# Bottom_board.net
KiCad netlist of a schematic drawn in Altium Designer
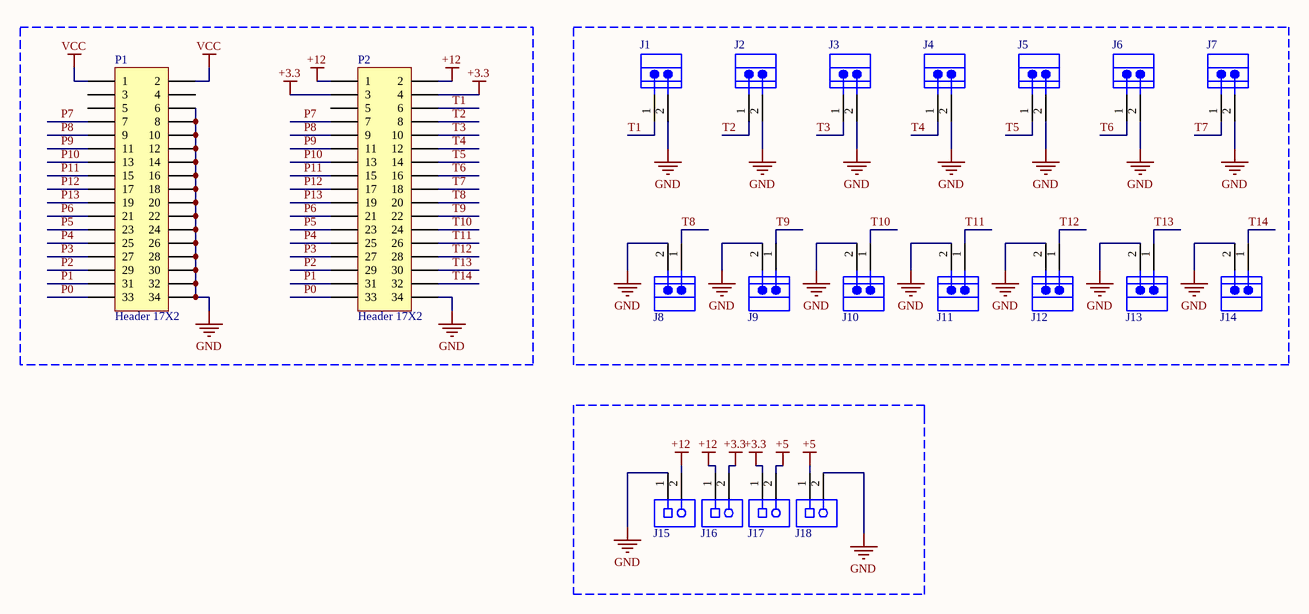
[diagram p0: Bottom_board.SchDoc]

(export (version "E")
  (design (tool "Eeschema 10.0.6"))
  (components
    (comp (ref "J1")
      (value "~")
      (footprint "KF350-3.5-02P")
      (fields
        (field (name "MANUFACTURER") "Cixi KaiFeng")
        (field (name "PARTNUMBER") "KF120-02P-14")
        (field (name "CONTACT") "Brass")
      )
      (libsource (lib "altium-import") (part "root_0_Terminal_2_"))
    )
    (comp (ref "J2")
      (value "~")
      (footprint "KF350-3.5-02P")
      (fields
        (field (name "MANUFACTURER") "Cixi KaiFeng")
        (field (name "PARTNUMBER") "KF120-02P-14")
        (field (name "CONTACT") "Brass")
      )
      (libsource (lib "altium-import") (part "root_0_Terminal_2_"))
    )
    (comp (ref "J3")
      (value "~")
      (footprint "KF350-3.5-02P")
      (fields
        (field (name "MANUFACTURER") "Cixi KaiFeng")
        (field (name "PARTNUMBER") "KF120-02P-14")
        (field (name "CONTACT") "Brass")
      )
      (libsource (lib "altium-import") (part "root_0_Terminal_2_"))
    )
    (comp (ref "J4")
      (value "~")
      (footprint "KF350-3.5-02P")
      (fields
        (field (name "MANUFACTURER") "Cixi KaiFeng")
        (field (name "PARTNUMBER") "KF120-02P-14")
        (field (name "CONTACT") "Brass")
      )
      (libsource (lib "altium-import") (part "root_0_Terminal_2_"))
    )
    (comp (ref "J5")
      (value "~")
      (footprint "KF350-3.5-02P")
      (fields
        (field (name "MANUFACTURER") "Cixi KaiFeng")
        (field (name "PARTNUMBER") "KF120-02P-14")
        (field (name "CONTACT") "Brass")
      )
      (libsource (lib "altium-import") (part "root_0_Terminal_2_"))
    )
    (comp (ref "J6")
      (value "~")
      (footprint "KF350-3.5-02P")
      (fields
        (field (name "MANUFACTURER") "Cixi KaiFeng")
        (field (name "PARTNUMBER") "KF120-02P-14")
        (field (name "CONTACT") "Brass")
      )
      (libsource (lib "altium-import") (part "root_0_Terminal_2_"))
    )
    (comp (ref "J7")
      (value "~")
      (footprint "KF350-3.5-02P")
      (fields
        (field (name "MANUFACTURER") "Cixi KaiFeng")
        (field (name "PARTNUMBER") "KF120-02P-14")
        (field (name "CONTACT") "Brass")
      )
      (libsource (lib "altium-import") (part "root_0_Terminal_2_"))
    )
    (comp (ref "J8")
      (value "~")
      (footprint "KF350-3.5-02P")
      (fields
        (field (name "MANUFACTURER") "Cixi KaiFeng")
        (field (name "PARTNUMBER") "KF120-02P-14")
        (field (name "CONTACT") "Brass")
      )
      (libsource (lib "altium-import") (part "root_2_Terminal_2_"))
    )
    (comp (ref "J9")
      (value "~")
      (footprint "KF350-3.5-02P")
      (fields
        (field (name "MANUFACTURER") "Cixi KaiFeng")
        (field (name "PARTNUMBER") "KF120-02P-14")
        (field (name "CONTACT") "Brass")
      )
      (libsource (lib "altium-import") (part "root_2_Terminal_2_"))
    )
    (comp (ref "J10")
      (value "~")
      (footprint "KF350-3.5-02P")
      (fields
        (field (name "MANUFACTURER") "Cixi KaiFeng")
        (field (name "PARTNUMBER") "KF120-02P-14")
        (field (name "CONTACT") "Brass")
      )
      (libsource (lib "altium-import") (part "root_2_Terminal_2_"))
    )
    (comp (ref "J11")
      (value "~")
      (footprint "KF350-3.5-02P")
      (fields
        (field (name "MANUFACTURER") "Cixi KaiFeng")
        (field (name "PARTNUMBER") "KF120-02P-14")
        (field (name "CONTACT") "Brass")
      )
      (libsource (lib "altium-import") (part "root_2_Terminal_2_"))
    )
    (comp (ref "J12")
      (value "~")
      (footprint "KF350-3.5-02P")
      (fields
        (field (name "MANUFACTURER") "Cixi KaiFeng")
        (field (name "PARTNUMBER") "KF120-02P-14")
        (field (name "CONTACT") "Brass")
      )
      (libsource (lib "altium-import") (part "root_2_Terminal_2_"))
    )
    (comp (ref "J13")
      (value "~")
      (footprint "KF350-3.5-02P")
      (fields
        (field (name "MANUFACTURER") "Cixi KaiFeng")
        (field (name "PARTNUMBER") "KF120-02P-14")
        (field (name "CONTACT") "Brass")
      )
      (libsource (lib "altium-import") (part "root_2_Terminal_2_"))
    )
    (comp (ref "J14")
      (value "~")
      (footprint "KF350-3.5-02P")
      (fields
        (field (name "MANUFACTURER") "Cixi KaiFeng")
        (field (name "PARTNUMBER") "KF120-02P-14")
        (field (name "CONTACT") "Brass")
      )
      (libsource (lib "altium-import") (part "root_2_Terminal_2_"))
    )
    (comp (ref "J15")
      (value "~")
      (footprint "PHOE-1729128-2_V")
      (description "PCB Terminal Block, 13.5 A, 400 V, 2-Pin THD, RoHS, Bulk")
      (fields (field (name "PARTNUMBER") "1729128") (field (name "MANUFACTURER") "Phoenix Contact"))
      (libsource (lib "altium-import") (part "root_3_mirrored_Terminal_2_Green_"))
    )
    (comp (ref "J16")
      (value "~")
      (footprint "PHOE-1729128-2_V")
      (description "PCB Terminal Block, 13.5 A, 400 V, 2-Pin THD, RoHS, Bulk")
      (fields (field (name "PARTNUMBER") "1729128") (field (name "MANUFACTURER") "Phoenix Contact"))
      (libsource (lib "altium-import") (part "root_3_mirrored_Terminal_2_Green_"))
    )
    (comp (ref "J17")
      (value "~")
      (footprint "PHOE-1729128-2_V")
      (description "PCB Terminal Block, 13.5 A, 400 V, 2-Pin THD, RoHS, Bulk")
      (fields (field (name "PARTNUMBER") "1729128") (field (name "MANUFACTURER") "Phoenix Contact"))
      (libsource (lib "altium-import") (part "root_3_mirrored_Terminal_2_Green_"))
    )
    (comp (ref "J18")
      (value "~")
      (footprint "PHOE-1729128-2_V")
      (description "PCB Terminal Block, 13.5 A, 400 V, 2-Pin THD, RoHS, Bulk")
      (fields (field (name "PARTNUMBER") "1729128") (field (name "MANUFACTURER") "Phoenix Contact"))
      (libsource (lib "altium-import") (part "root_3_mirrored_Terminal_2_Green_"))
    )
    (comp (ref "P1")
      (value "Header 17X2")
      (footprint "HDR2X17")
      (description "Header, 17-Pin, Dual row")
      (fields (field (name "PUBLISHER") "Altium Limited"))
      (libsource (lib "altium-import") (part "root_0_Header 17X2_"))
    )
    (comp (ref "P2")
      (value "Header 17X2")
      (footprint "HDR2X17-PBD")
      (description "Header, 17-Pin, Dual row")
      (fields (field (name "PUBLISHER") "Altium Limited"))
      (libsource (lib "altium-import") (part "root_0_Header 17X2_"))
    )
  )
  (nets
    (net (code "1") (name "+3.3") (class "Default")
      (node (ref "J16") (pin "2") (pinfunction "2_2") (pintype "passive"))
      (node (ref "J17") (pin "1") (pinfunction "1_1") (pintype "passive"))
      (node (ref "P2") (pin "3") (pinfunction "3_3") (pintype "passive"))
      (node (ref "P2") (pin "4") (pinfunction "4_4") (pintype "passive"))
    )
    (net (code "2") (name "+5") (class "Default")
      (node (ref "J17") (pin "2") (pinfunction "2_2") (pintype "passive"))
      (node (ref "J18") (pin "1") (pinfunction "1_1") (pintype "passive"))
    )
    (net (code "3") (name "+12") (class "Default")
      (node (ref "J15") (pin "2") (pinfunction "2_2") (pintype "passive"))
      (node (ref "J16") (pin "1") (pinfunction "1_1") (pintype "passive"))
      (node (ref "P2") (pin "1") (pinfunction "1_1") (pintype "passive"))
      (node (ref "P2") (pin "2") (pinfunction "2_2") (pintype "passive"))
    )
    (net (code "4") (name "/P0") (class "Default")
      (node (ref "P1") (pin "33") (pinfunction "33_33") (pintype "passive"))
      (node (ref "P2") (pin "33") (pinfunction "33_33") (pintype "passive"))
    )
    (net (code "5") (name "/P1") (class "Default")
      (node (ref "P1") (pin "31") (pinfunction "31_31") (pintype "passive"))
      (node (ref "P2") (pin "31") (pinfunction "31_31") (pintype "passive"))
    )
    (net (code "6") (name "/P2") (class "Default")
      (node (ref "P1") (pin "29") (pinfunction "29_29") (pintype "passive"))
      (node (ref "P2") (pin "29") (pinfunction "29_29") (pintype "passive"))
    )
    (net (code "7") (name "/P3") (class "Default")
      (node (ref "P1") (pin "27") (pinfunction "27_27") (pintype "passive"))
      (node (ref "P2") (pin "27") (pinfunction "27_27") (pintype "passive"))
    )
    (net (code "8") (name "/P4") (class "Default")
      (node (ref "P1") (pin "25") (pinfunction "25_25") (pintype "passive"))
      (node (ref "P2") (pin "25") (pinfunction "25_25") (pintype "passive"))
    )
    (net (code "9") (name "/P5") (class "Default")
      (node (ref "P1") (pin "23") (pinfunction "23_23") (pintype "passive"))
      (node (ref "P2") (pin "23") (pinfunction "23_23") (pintype "passive"))
    )
    (net (code "10") (name "/P6") (class "Default")
      (node (ref "P1") (pin "21") (pinfunction "21_21") (pintype "passive"))
      (node (ref "P2") (pin "21") (pinfunction "21_21") (pintype "passive"))
    )
    (net (code "11") (name "/P7") (class "Default")
      (node (ref "P1") (pin "7") (pinfunction "7_7") (pintype "passive"))
      (node (ref "P2") (pin "7") (pinfunction "7_7") (pintype "passive"))
    )
    (net (code "12") (name "/P8") (class "Default")
      (node (ref "P1") (pin "9") (pinfunction "9_9") (pintype "passive"))
      (node (ref "P2") (pin "9") (pinfunction "9_9") (pintype "passive"))
    )
    (net (code "13") (name "/P9") (class "Default")
      (node (ref "P1") (pin "11") (pinfunction "11_11") (pintype "passive"))
      (node (ref "P2") (pin "11") (pinfunction "11_11") (pintype "passive"))
    )
    (net (code "14") (name "/P10") (class "Default")
      (node (ref "P1") (pin "13") (pinfunction "13_13") (pintype "passive"))
      (node (ref "P2") (pin "13") (pinfunction "13_13") (pintype "passive"))
    )
    (net (code "15") (name "/P11") (class "Default")
      (node (ref "P1") (pin "15") (pinfunction "15_15") (pintype "passive"))
      (node (ref "P2") (pin "15") (pinfunction "15_15") (pintype "passive"))
    )
    (net (code "16") (name "/P12") (class "Default")
      (node (ref "P1") (pin "17") (pinfunction "17_17") (pintype "passive"))
      (node (ref "P2") (pin "17") (pinfunction "17_17") (pintype "passive"))
    )
    (net (code "17") (name "/P13") (class "Default")
      (node (ref "P1") (pin "19") (pinfunction "19_19") (pintype "passive"))
      (node (ref "P2") (pin "19") (pinfunction "19_19") (pintype "passive"))
    )
    (net (code "18") (name "/T1") (class "Default")
      (node (ref "J1") (pin "1") (pinfunction "1_1") (pintype "passive"))
      (node (ref "P2") (pin "6") (pinfunction "6_6") (pintype "passive"))
    )
    (net (code "19") (name "/T2") (class "Default")
      (node (ref "J2") (pin "1") (pinfunction "1_1") (pintype "passive"))
      (node (ref "P2") (pin "8") (pinfunction "8_8") (pintype "passive"))
    )
    (net (code "20") (name "/T3") (class "Default")
      (node (ref "J3") (pin "1") (pinfunction "1_1") (pintype "passive"))
      (node (ref "P2") (pin "10") (pinfunction "10_10") (pintype "passive"))
    )
    (net (code "21") (name "/T4") (class "Default")
      (node (ref "J4") (pin "1") (pinfunction "1_1") (pintype "passive"))
      (node (ref "P2") (pin "12") (pinfunction "12_12") (pintype "passive"))
    )
    (net (code "22") (name "/T5") (class "Default")
      (node (ref "J5") (pin "1") (pinfunction "1_1") (pintype "passive"))
      (node (ref "P2") (pin "14") (pinfunction "14_14") (pintype "passive"))
    )
    (net (code "23") (name "/T6") (class "Default")
      (node (ref "J6") (pin "1") (pinfunction "1_1") (pintype "passive"))
      (node (ref "P2") (pin "16") (pinfunction "16_16") (pintype "passive"))
    )
    (net (code "24") (name "/T7") (class "Default")
      (node (ref "J7") (pin "1") (pinfunction "1_1") (pintype "passive"))
      (node (ref "P2") (pin "18") (pinfunction "18_18") (pintype "passive"))
    )
    (net (code "25") (name "/T8") (class "Default")
      (node (ref "J8") (pin "1") (pinfunction "1_1") (pintype "passive"))
      (node (ref "P2") (pin "20") (pinfunction "20_20") (pintype "passive"))
    )
    (net (code "26") (name "/T9") (class "Default")
      (node (ref "J9") (pin "1") (pinfunction "1_1") (pintype "passive"))
      (node (ref "P2") (pin "22") (pinfunction "22_22") (pintype "passive"))
    )
    (net (code "27") (name "/T10") (class "Default")
      (node (ref "J10") (pin "1") (pinfunction "1_1") (pintype "passive"))
      (node (ref "P2") (pin "24") (pinfunction "24_24") (pintype "passive"))
    )
    (net (code "28") (name "/T11") (class "Default")
      (node (ref "J11") (pin "1") (pinfunction "1_1") (pintype "passive"))
      (node (ref "P2") (pin "26") (pinfunction "26_26") (pintype "passive"))
    )
    (net (code "29") (name "/T12") (class "Default")
      (node (ref "J12") (pin "1") (pinfunction "1_1") (pintype "passive"))
      (node (ref "P2") (pin "28") (pinfunction "28_28") (pintype "passive"))
    )
    (net (code "30") (name "/T13") (class "Default")
      (node (ref "J13") (pin "1") (pinfunction "1_1") (pintype "passive"))
      (node (ref "P2") (pin "30") (pinfunction "30_30") (pintype "passive"))
    )
    (net (code "31") (name "/T14") (class "Default")
      (node (ref "J14") (pin "1") (pinfunction "1_1") (pintype "passive"))
      (node (ref "P2") (pin "32") (pinfunction "32_32") (pintype "passive"))
    )
    (net (code "32") (name "GND") (class "Default")
      (node (ref "J1") (pin "2") (pinfunction "2_2") (pintype "passive"))
      (node (ref "J10") (pin "2") (pinfunction "2_2") (pintype "passive"))
      (node (ref "J11") (pin "2") (pinfunction "2_2") (pintype "passive"))
      (node (ref "J12") (pin "2") (pinfunction "2_2") (pintype "passive"))
      (node (ref "J13") (pin "2") (pinfunction "2_2") (pintype "passive"))
      (node (ref "J14") (pin "2") (pinfunction "2_2") (pintype "passive"))
      (node (ref "J15") (pin "1") (pinfunction "1_1") (pintype "passive"))
      (node (ref "J18") (pin "2") (pinfunction "2_2") (pintype "passive"))
      (node (ref "J2") (pin "2") (pinfunction "2_2") (pintype "passive"))
      (node (ref "J3") (pin "2") (pinfunction "2_2") (pintype "passive"))
      (node (ref "J4") (pin "2") (pinfunction "2_2") (pintype "passive"))
      (node (ref "J5") (pin "2") (pinfunction "2_2") (pintype "passive"))
      (node (ref "J6") (pin "2") (pinfunction "2_2") (pintype "passive"))
      (node (ref "J7") (pin "2") (pinfunction "2_2") (pintype "passive"))
      (node (ref "J8") (pin "2") (pinfunction "2_2") (pintype "passive"))
      (node (ref "J9") (pin "2") (pinfunction "2_2") (pintype "passive"))
      (node (ref "P1") (pin "10") (pinfunction "10_10") (pintype "passive"))
      (node (ref "P1") (pin "12") (pinfunction "12_12") (pintype "passive"))
      (node (ref "P1") (pin "14") (pinfunction "14_14") (pintype "passive"))
      (node (ref "P1") (pin "16") (pinfunction "16_16") (pintype "passive"))
      (node (ref "P1") (pin "18") (pinfunction "18_18") (pintype "passive"))
      (node (ref "P1") (pin "20") (pinfunction "20_20") (pintype "passive"))
      (node (ref "P1") (pin "22") (pinfunction "22_22") (pintype "passive"))
      (node (ref "P1") (pin "24") (pinfunction "24_24") (pintype "passive"))
      (node (ref "P1") (pin "26") (pinfunction "26_26") (pintype "passive"))
      (node (ref "P1") (pin "28") (pinfunction "28_28") (pintype "passive"))
      (node (ref "P1") (pin "30") (pinfunction "30_30") (pintype "passive"))
      (node (ref "P1") (pin "32") (pinfunction "32_32") (pintype "passive"))
      (node (ref "P1") (pin "34") (pinfunction "34_34") (pintype "passive"))
      (node (ref "P1") (pin "6") (pinfunction "6_6") (pintype "passive"))
      (node (ref "P1") (pin "8") (pinfunction "8_8") (pintype "passive"))
      (node (ref "P2") (pin "34") (pinfunction "34_34") (pintype "passive"))
    )
    (net (code "33") (name "VCC") (class "Default")
      (node (ref "P1") (pin "1") (pinfunction "1_1") (pintype "passive"))
      (node (ref "P1") (pin "2") (pinfunction "2_2") (pintype "passive"))
    )
    (net (code "34") (name "unconnected-(P1-Pad3)") (class "Default")
      (node (ref "P1") (pin "3") (pinfunction "3_3") (pintype "passive"))
    )
    (net (code "35") (name "unconnected-(P1-Pad4)") (class "Default")
      (node (ref "P1") (pin "4") (pinfunction "4_4") (pintype "passive"))
    )
    (net (code "36") (name "unconnected-(P1-Pad5)") (class "Default")
      (node (ref "P1") (pin "5") (pinfunction "5_5") (pintype "passive"))
    )
    (net (code "37") (name "unconnected-(P2-Pad5)") (class "Default")
      (node (ref "P2") (pin "5") (pinfunction "5_5") (pintype "passive"))
    )
  )
)
